# P02_Power_Management.net
KiCad netlist of a schematic drawn in Altium Designer
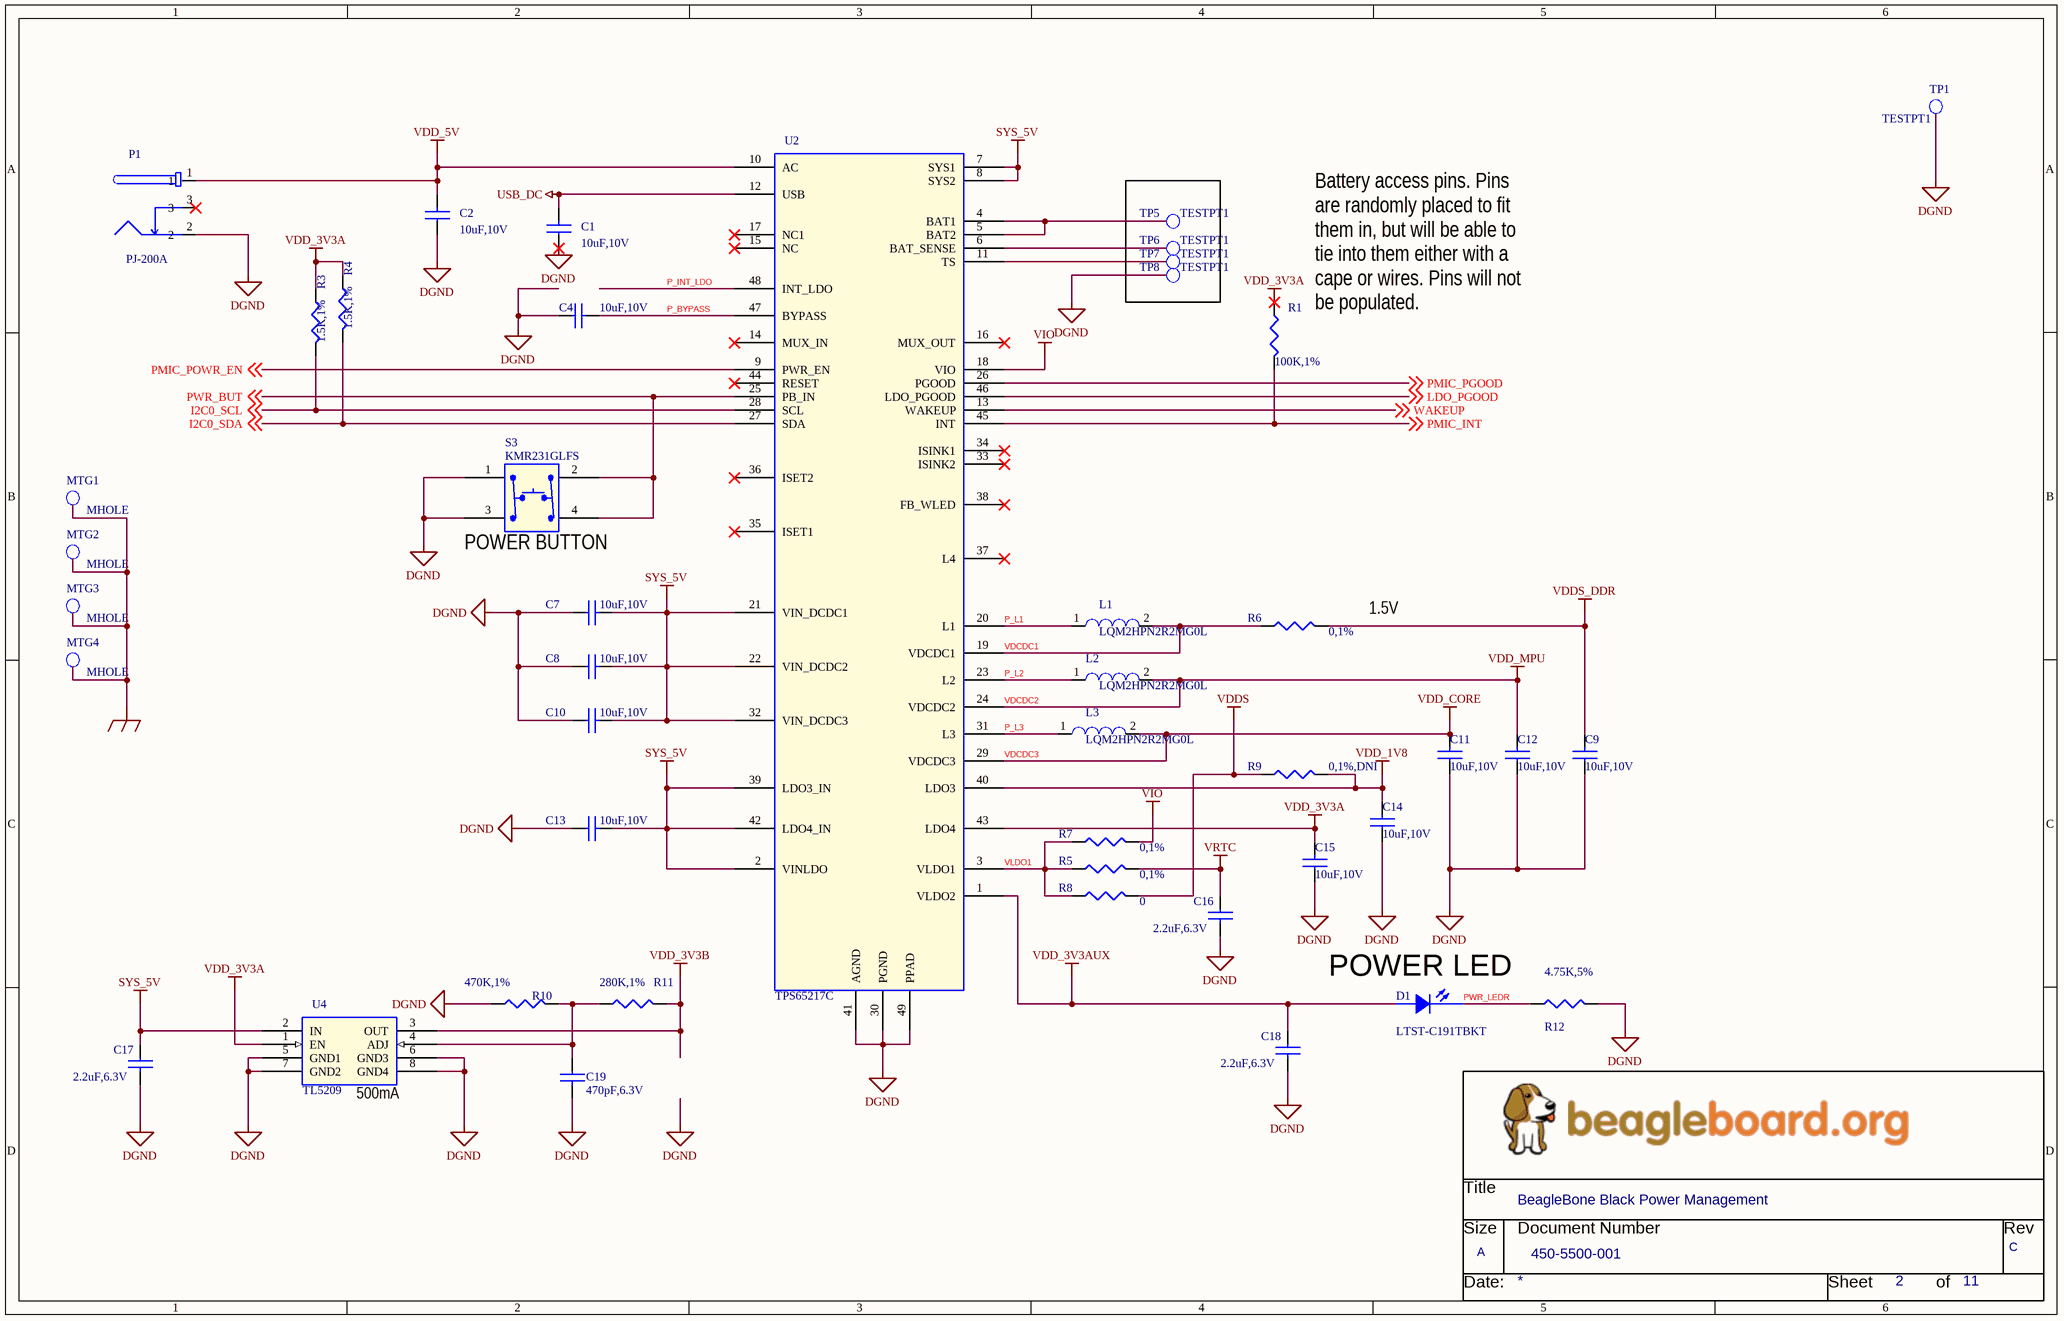
[diagram p0: P02_Power Management.SchDoc]

(export (version "E")
  (design (tool "Eeschema 10.0.6"))
  (components
    (comp (ref "C1")
      (value "10uF,10V")
      (footprint "r402-25rd")
      (fields (field (name "PART NUMBER") "CAP_10uF_Y5V_10V_10%_0805"))
      (libsource (lib "*") (part "CAP_10uF_Y5V_10V_10%_0805"))
    )
    (comp (ref "C2")
      (value "10uF,10V")
      (footprint "r402-25rd")
      (fields (field (name "PART NUMBER") "CAP_10uF_Y5V_10V_10%_0805"))
      (libsource (lib "*") (part "CAP_10uF_Y5V_10V_10%_0805"))
    )
    (comp (ref "C4")
      (value "10uF,10V")
      (footprint "r402-25rd")
      (fields (field (name "PART NUMBER") "CAP_10uF_Y5V_10V_10%_0805"))
      (libsource (lib "*") (part "CAP_10uF_Y5V_10V_10%_0805"))
    )
    (comp (ref "C7")
      (value "10uF,10V")
      (footprint "r402-25rd")
      (fields (field (name "PART NUMBER") "CAP_10uF_Y5V_10V_10%_0805"))
      (libsource (lib "*") (part "CAP_10uF_Y5V_10V_10%_0805"))
    )
    (comp (ref "C8")
      (value "10uF,10V")
      (footprint "r402-25rd")
      (fields (field (name "PART NUMBER") "CAP_10uF_Y5V_10V_10%_0805"))
      (libsource (lib "*") (part "CAP_10uF_Y5V_10V_10%_0805"))
    )
    (comp (ref "C9")
      (value "10uF,10V")
      (footprint "r402-25rd")
      (fields (field (name "PART NUMBER") "CAP_10uF_Y5V_10V_10%_0805"))
      (libsource (lib "*") (part "CAP_10uF_Y5V_10V_10%_0805"))
    )
    (comp (ref "C10")
      (value "10uF,10V")
      (footprint "r402-25rd")
      (fields (field (name "PART NUMBER") "CAP_10uF_Y5V_10V_10%_0805"))
      (libsource (lib "*") (part "CAP_10uF_Y5V_10V_10%_0805"))
    )
    (comp (ref "C11")
      (value "10uF,10V")
      (footprint "r402-25rd")
      (fields (field (name "PART NUMBER") "CAP_10uF_Y5V_10V_10%_0805"))
      (libsource (lib "*") (part "CAP_10uF_Y5V_10V_10%_0805"))
    )
    (comp (ref "C12")
      (value "10uF,10V")
      (footprint "r402-25rd")
      (fields (field (name "PART NUMBER") "CAP_10uF_Y5V_10V_10%_0805"))
      (libsource (lib "*") (part "CAP_10uF_Y5V_10V_10%_0805"))
    )
    (comp (ref "C13")
      (value "10uF,10V")
      (footprint "r402-25rd")
      (fields (field (name "PART NUMBER") "CAP_10uF_Y5V_10V_10%_0805"))
      (libsource (lib "*") (part "CAP_10uF_Y5V_10V_10%_0805"))
    )
    (comp (ref "C14")
      (value "10uF,10V")
      (footprint "r402-25rd")
      (fields (field (name "PART NUMBER") "CAP_10uF_Y5V_10V_10%_0805"))
      (libsource (lib "*") (part "CAP_10uF_Y5V_10V_10%_0805"))
    )
    (comp (ref "C15")
      (value "10uF,10V")
      (footprint "r402-25rd")
      (fields (field (name "PART NUMBER") "CAP_10uF_Y5V_10V_10%_0805"))
      (libsource (lib "*") (part "CAP_10uF_Y5V_10V_10%_0805"))
    )
    (comp (ref "C16")
      (value "2.2uF,6.3V")
      (footprint "402")
      (fields (field (name "PART NUMBER") "CAP_2.2uF_X5R_6.3V_10%_0402"))
      (libsource (lib "*") (part "CAP_2.2uF_X5R_6.3V_10%_0402"))
    )
    (comp (ref "C17")
      (value "2.2uF,6.3V")
      (footprint "402")
      (fields (field (name "PART NUMBER") "CAP_2.2uF_X5R_6.3V_10%_0402"))
      (libsource (lib "*") (part "CAP_2.2uF_X5R_6.3V_10%_0402"))
    )
    (comp (ref "C18")
      (value "2.2uF,6.3V")
      (footprint "402")
      (fields (field (name "PART NUMBER") "CAP_2.2uF_X5R_6.3V_10%_0402"))
      (libsource (lib "*") (part "CAP_2.2uF_X5R_6.3V_10%_0402"))
    )
    (comp (ref "C19")
      (value "470pF,6.3V")
      (footprint "402")
      (fields (field (name "PART NUMBER") "CAP_470PF_X7R_25V_10%_0402"))
      (libsource (lib "*") (part "CAP_470PF_X7R_25V_10%_0402"))
    )
    (comp (ref "D1")
      (value "LTST-C191TBKT")
      (footprint "led1206-59x59")
      (libsource (lib "*") (part "LED_LTST-C150GKT_0"))
    )
    (comp (ref "L1")
      (value "LQM2HPN2R2MG0L")
      (footprint "VLCF5020T")
      (description "Inductor 2.2uH smt 2.6A, 58 milliohm")
      (fields (field (name "TIINTPARTNUMBER") "1L0025") (field (name "MFR") "TDK"))
      (libsource (lib "*") (part "IND_2.2uH_2.6A_10%_SMD"))
    )
    (comp (ref "L2")
      (value "LQM2HPN2R2MG0L")
      (footprint "VLCF5020T")
      (description "Inductor 2.2uH smt 2.6A, 58 milliohm")
      (fields (field (name "TIINTPARTNUMBER") "1L0025") (field (name "MFR") "TDK"))
      (libsource (lib "*") (part "IND_2.2uH_2.6A_10%_SMD"))
    )
    (comp (ref "L3")
      (value "LQM2HPN2R2MG0L")
      (footprint "VLCF5020T")
      (description "Inductor 2.2uH smt 2.6A, 58 milliohm")
      (fields (field (name "TIINTPARTNUMBER") "1L0025") (field (name "MFR") "TDK"))
      (libsource (lib "*") (part "IND_2.2uH_2.6A_10%_SMD"))
    )
    (comp (ref "MTG1") (value "MHOLE") (footprint "mh230-156") (libsource (lib "*") (part "MHOLE")))
    (comp (ref "MTG2") (value "MHOLE") (footprint "mh230-156") (libsource (lib "*") (part "MHOLE")))
    (comp (ref "MTG3") (value "MHOLE") (footprint "mh230-156") (libsource (lib "*") (part "MHOLE")))
    (comp (ref "MTG4") (value "MHOLE") (footprint "mh230-156") (libsource (lib "*") (part "MHOLE")))
    (comp (ref "P1")
      (value "PJ-200A")
      (footprint "CONN3-PWR-PJ102A")
      (libsource (lib "*") (part "Power_Jack"))
    )
    (comp (ref "R1")
      (value "100K,1%")
      (footprint "402")
      (description "Resistor 100Kohm 1/16W 1% 0402")
      (fields (field (name "PART NUMBER") "RES_100K_1/16W_1%_0402"))
      (libsource (lib "*") (part "RES_100K_1/16W_1%_0402"))
    )
    (comp (ref "R3")
      (value "1.5K,1%")
      (footprint "402")
      (description "RES 1.5K OHM 1/16W 5% 0402 SMD")
      (fields (field (name "PART NUMBER") "RES_1.5K_1/16W_5%_0402"))
      (libsource (lib "*") (part "RES_1.5K_1/16W_5%_0402_Dup1"))
    )
    (comp (ref "R4")
      (value "1.5K,1%")
      (footprint "402")
      (description "RES 1.5K OHM 1/16W 5% 0402 SMD")
      (fields (field (name "PART NUMBER") "RES_1.5K_1/16W_5%_0402"))
      (libsource (lib "*") (part "RES_1.5K_1/16W_5%_0402_Dup1"))
    )
    (comp (ref "R5")
      (value "0,1%")
      (footprint "402")
      (description "RES 4.75K OHM 1/16W 1% 0402 SMD")
      (fields (field (name "PART NUMBER") "RES_4.75K_1/16W_1%_0402"))
      (libsource (lib "*") (part "RES_4.75K_1/16W_1%_0402"))
    )
    (comp (ref "R6")
      (value "0,1%")
      (footprint "402")
      (description "RES 4.75K OHM 1/16W 1% 0402 SMD")
      (fields (field (name "PART NUMBER") "RES_4.75K_1/16W_1%_0402"))
      (libsource (lib "*") (part "RES_4.75K_1/16W_1%_0402"))
    )
    (comp (ref "R7")
      (value "0,1%")
      (footprint "402")
      (description "RES 4.75K OHM 1/16W 1% 0402 SMD")
      (fields (field (name "PART NUMBER") "RES_4.75K_1/16W_1%_0402"))
      (libsource (lib "*") (part "RES_4.75K_1/16W_1%_0402"))
    )
    (comp (ref "R8")
      (value "0")
      (footprint "402")
      (description "RES 4.75K OHM 1/16W 1% 0402 SMD")
      (fields (field (name "PART NUMBER") "RES_4.75K_1/16W_1%_0402"))
      (libsource (lib "*") (part "RES_4.75K_1/16W_1%_0402"))
    )
    (comp (ref "R9")
      (value "0,1%,DNI")
      (footprint "402")
      (description "RES 4.75K OHM 1/16W 1% 0402 SMD")
      (fields (field (name "PART NUMBER") "RES_4.75K_1/16W_1%_0402"))
      (libsource (lib "*") (part "RES_4.75K_1/16W_1%_0402"))
    )
    (comp (ref "R10")
      (value "470K,1%")
      (footprint "402")
      (description "RES 470 OHM 1/10W 5% 0402 SMD")
      (fields (field (name "PART NUMBER") "RES_470_1/10W_5%_0402"))
      (libsource (lib "*") (part "RES_470_1/10W_5%_0402"))
    )
    (comp (ref "R11")
      (value "280K,1%")
      (footprint "402")
      (description "RES 470 OHM 1/10W 5% 0402 SMD")
      (fields (field (name "PART NUMBER") "RES_470_1/10W_5%_0402"))
      (libsource (lib "*") (part "RES_470_1/10W_5%_0402"))
    )
    (comp (ref "R12")
      (value "4.75K,5%")
      (footprint "402")
      (description "RES 470 OHM 1/10W 5% 0402 SMD")
      (fields (field (name "PART NUMBER") "RES_470_1/10W_5%_0402"))
      (libsource (lib "*") (part "RES_470_1/10W_5%_0402"))
    )
    (comp (ref "S3")
      (value "KMR231GLFS")
      (footprint "SM-SW-SPST-4-4")
      (libsource (lib "*") (part "SW_KT11P2JM_2"))
    )
    (comp (ref "TP1") (value "TESTPT1") (footprint "tp1-8040") (libsource (lib "*") (part "TESTPT1")))
    (comp (ref "TP5") (value "TESTPT1") (footprint "tp1-8040") (libsource (lib "*") (part "TESTPT1")))
    (comp (ref "TP6") (value "TESTPT1") (footprint "tp1-8040") (libsource (lib "*") (part "TESTPT1")))
    (comp (ref "TP7") (value "TESTPT1") (footprint "tp1-8040") (libsource (lib "*") (part "TESTPT1")))
    (comp (ref "TP8") (value "TESTPT1") (footprint "tp1-8040") (libsource (lib "*") (part "TESTPT1")))
    (comp (ref "U2") (value "TPS65217C") (footprint "TBD") (libsource (lib "*") (part "PWR_TPS65217_2")))
    (comp (ref "U4")
      (value "TL5209")
      (footprint "SO8-25X75")
      (libsource (lib "*") (part "PWR_TLV70233DBV_0"))
    )
  )
  (nets
    (net (code "1") (name "/PWR_LEDR") (class "Default")
      (node (ref "D1") (pin "1") (pinfunction "C_1") (pintype "passive"))
      (node (ref "R12") (pin "2") (pinfunction "2_2") (pintype "passive"))
    )
    (net (code "2") (name "/P_BYPASS") (class "Default")
      (node (ref "C4") (pin "2") (pinfunction "2_2") (pintype "passive"))
      (node (ref "U2") (pin "47") (pinfunction "BYPASS_47") (pintype "passive"))
    )
    (net (code "3") (name "/P_INT_LDO") (class "Default")
      (node (ref "U2") (pin "48") (pinfunction "INT_LDO_48") (pintype "passive"))
    )
    (net (code "4") (name "/P_L1") (class "Default")
      (node (ref "L1") (pin "1") (pinfunction "1_1") (pintype "passive"))
      (node (ref "U2") (pin "20") (pinfunction "L1_20") (pintype "passive"))
    )
    (net (code "5") (name "/P_L2") (class "Default")
      (node (ref "L2") (pin "1") (pinfunction "1_1") (pintype "passive"))
      (node (ref "U2") (pin "23") (pinfunction "L2_23") (pintype "passive"))
    )
    (net (code "6") (name "/P_L3") (class "Default")
      (node (ref "L3") (pin "1") (pinfunction "1_1") (pintype "passive"))
      (node (ref "U2") (pin "31") (pinfunction "L3_31") (pintype "passive"))
    )
    (net (code "7") (name "/VDCDC1") (class "Default")
      (node (ref "L1") (pin "2") (pinfunction "2_2") (pintype "passive"))
      (node (ref "R6") (pin "1") (pinfunction "1_1") (pintype "passive"))
      (node (ref "U2") (pin "19") (pinfunction "VDCDC1_19") (pintype "passive"))
    )
    (net (code "8") (name "/VLDO1") (class "Default")
      (node (ref "R5") (pin "1") (pinfunction "1_1") (pintype "passive"))
      (node (ref "R7") (pin "1") (pinfunction "1_1") (pintype "passive"))
      (node (ref "R8") (pin "1") (pinfunction "1_1") (pintype "passive"))
      (node (ref "U2") (pin "3") (pinfunction "VLDO1_3") (pintype "passive"))
    )
    (net (code "9") (name "DGND") (class "Default")
      (node (ref "C1") (pin "1") (pinfunction "1_1") (pintype "passive"))
      (node (ref "C10") (pin "1") (pinfunction "1_1") (pintype "passive"))
      (node (ref "C11") (pin "1") (pinfunction "1_1") (pintype "passive"))
      (node (ref "C12") (pin "1") (pinfunction "1_1") (pintype "passive"))
      (node (ref "C13") (pin "1") (pinfunction "1_1") (pintype "passive"))
      (node (ref "C14") (pin "1") (pinfunction "1_1") (pintype "passive"))
      (node (ref "C15") (pin "1") (pinfunction "1_1") (pintype "passive"))
      (node (ref "C16") (pin "2") (pinfunction "2_2") (pintype "passive"))
      (node (ref "C17") (pin "2") (pinfunction "2_2") (pintype "passive"))
      (node (ref "C18") (pin "2") (pinfunction "2_2") (pintype "passive"))
      (node (ref "C19") (pin "2") (pinfunction "2_2") (pintype "passive"))
      (node (ref "C2") (pin "1") (pinfunction "1_1") (pintype "passive"))
      (node (ref "C4") (pin "1") (pinfunction "1_1") (pintype "passive"))
      (node (ref "C7") (pin "1") (pinfunction "1_1") (pintype "passive"))
      (node (ref "C8") (pin "1") (pinfunction "1_1") (pintype "passive"))
      (node (ref "C9") (pin "1") (pinfunction "1_1") (pintype "passive"))
      (node (ref "P1") (pin "2") (pinfunction "2_2") (pintype "passive"))
      (node (ref "R10") (pin "2") (pinfunction "2_2") (pintype "passive"))
      (node (ref "R12") (pin "1") (pinfunction "1_1") (pintype "passive"))
      (node (ref "S3") (pin "1") (pinfunction "A1_1") (pintype "passive"))
      (node (ref "S3") (pin "3") (pinfunction "A2_3") (pintype "passive"))
      (node (ref "TP1") (pin "1") (pinfunction "TP_1") (pintype "passive"))
      (node (ref "TP8") (pin "1") (pinfunction "TP_1") (pintype "passive"))
      (node (ref "U2") (pin "30") (pinfunction "PGND_30") (pintype "passive"))
      (node (ref "U2") (pin "41") (pinfunction "AGND_41") (pintype "passive"))
      (node (ref "U2") (pin "49") (pinfunction "PPAD_49") (pintype "passive"))
      (node (ref "U4") (pin "5") (pinfunction "GND1_5") (pintype "power_in"))
      (node (ref "U4") (pin "6") (pinfunction "GND3_6") (pintype "power_in"))
      (node (ref "U4") (pin "7") (pinfunction "GND2_7") (pintype "power_in"))
      (node (ref "U4") (pin "8") (pinfunction "GND4_8") (pintype "power_in"))
    )
    (net (code "10") (name "GND_EARTH") (class "Default")
      (node (ref "MTG1") (pin "1") (pinfunction "TP_1") (pintype "passive"))
      (node (ref "MTG2") (pin "1") (pinfunction "TP_1") (pintype "passive"))
      (node (ref "MTG3") (pin "1") (pinfunction "TP_1") (pintype "passive"))
      (node (ref "MTG4") (pin "1") (pinfunction "TP_1") (pintype "passive"))
    )
    (net (code "11") (name "I2C0_SCL") (class "Default")
      (node (ref "R3") (pin "2") (pinfunction "2_2") (pintype "passive"))
      (node (ref "U2") (pin "28") (pinfunction "SCL_28") (pintype "passive"))
    )
    (net (code "12") (name "I2C0_SDA") (class "Default")
      (node (ref "R4") (pin "2") (pinfunction "2_2") (pintype "passive"))
      (node (ref "U2") (pin "27") (pinfunction "SDA_27") (pintype "passive"))
    )
    (net (code "13") (name "LDO_PGOOD") (class "Default")
      (node (ref "U2") (pin "46") (pinfunction "LDO_PGOOD_46") (pintype "passive"))
    )
    (net (code "14") (name "Net-(TP5-TP)") (class "Default")
      (node (ref "TP5") (pin "1") (pinfunction "TP_1") (pintype "passive"))
      (node (ref "U2") (pin "4") (pinfunction "BAT1_4") (pintype "passive"))
      (node (ref "U2") (pin "5") (pinfunction "BAT2_5") (pintype "passive"))
    )
    (net (code "15") (name "Net-(TP6-TP)") (class "Default")
      (node (ref "TP6") (pin "1") (pinfunction "TP_1") (pintype "passive"))
      (node (ref "U2") (pin "6") (pinfunction "BAT_SENSE_6") (pintype "passive"))
    )
    (net (code "16") (name "Net-(TP7-TP)") (class "Default")
      (node (ref "TP7") (pin "1") (pinfunction "TP_1") (pintype "passive"))
      (node (ref "U2") (pin "11") (pinfunction "TS_11") (pintype "passive"))
    )
    (net (code "17") (name "Net-(U4-ADJ)") (class "Default")
      (node (ref "C19") (pin "1") (pinfunction "1_1") (pintype "passive"))
      (node (ref "R10") (pin "1") (pinfunction "1_1") (pintype "passive"))
      (node (ref "R11") (pin "2") (pinfunction "2_2") (pintype "passive"))
      (node (ref "U4") (pin "4") (pinfunction "ADJ_4") (pintype "input"))
    )
    (net (code "18") (name "PMIC_INT") (class "Default")
      (node (ref "R1") (pin "2") (pinfunction "2_2") (pintype "passive"))
      (node (ref "U2") (pin "45") (pinfunction "INT_45") (pintype "passive"))
    )
    (net (code "19") (name "PMIC_PGOOD") (class "Default")
      (node (ref "U2") (pin "26") (pinfunction "PGOOD_26") (pintype "passive"))
    )
    (net (code "20") (name "PMIC_POWR_EN") (class "Default")
      (node (ref "U2") (pin "9") (pinfunction "PWR_EN_9") (pintype "passive"))
    )
    (net (code "21") (name "PWR_BUT") (class "Default")
      (node (ref "S3") (pin "2") (pinfunction "B1_2") (pintype "passive"))
      (node (ref "S3") (pin "4") (pinfunction "B2_4") (pintype "passive"))
      (node (ref "U2") (pin "25") (pinfunction "PB_IN_25") (pintype "passive"))
    )
    (net (code "22") (name "SYS_5V") (class "Default")
      (node (ref "C10") (pin "2") (pinfunction "2_2") (pintype "passive"))
      (node (ref "C13") (pin "2") (pinfunction "2_2") (pintype "passive"))
      (node (ref "C17") (pin "1") (pinfunction "1_1") (pintype "passive"))
      (node (ref "C7") (pin "2") (pinfunction "2_2") (pintype "passive"))
      (node (ref "C8") (pin "2") (pinfunction "2_2") (pintype "passive"))
      (node (ref "U2") (pin "2") (pinfunction "VINLDO_2") (pintype "passive"))
      (node (ref "U2") (pin "21") (pinfunction "VIN_DCDC1_21") (pintype "passive"))
      (node (ref "U2") (pin "22") (pinfunction "VIN_DCDC2_22") (pintype "passive"))
      (node (ref "U2") (pin "32") (pinfunction "VIN_DCDC3_32") (pintype "passive"))
      (node (ref "U2") (pin "39") (pinfunction "LDO3_IN_39") (pintype "passive"))
      (node (ref "U2") (pin "42") (pinfunction "LDO4_IN_42") (pintype "passive"))
      (node (ref "U2") (pin "7") (pinfunction "SYS1_7") (pintype "passive"))
      (node (ref "U2") (pin "8") (pinfunction "SYS2_8") (pintype "passive"))
      (node (ref "U4") (pin "2") (pinfunction "IN_2") (pintype "power_in"))
    )
    (net (code "23") (name "USB_DC") (class "Default")
      (node (ref "C1") (pin "2") (pinfunction "2_2") (pintype "passive"))
      (node (ref "U2") (pin "12") (pinfunction "USB_12") (pintype "passive"))
    )
    (net (code "24") (name "VDDS") (class "Default")
      (node (ref "R8") (pin "2") (pinfunction "2_2") (pintype "passive"))
      (node (ref "R9") (pin "1") (pinfunction "1_1") (pintype "passive"))
    )
    (net (code "25") (name "VDDS_DDR") (class "Default")
      (node (ref "C9") (pin "2") (pinfunction "2_2") (pintype "passive"))
      (node (ref "R6") (pin "2") (pinfunction "2_2") (pintype "passive"))
    )
    (net (code "26") (name "VDD_1V8") (class "Default")
      (node (ref "C14") (pin "2") (pinfunction "2_2") (pintype "passive"))
      (node (ref "R9") (pin "2") (pinfunction "2_2") (pintype "passive"))
      (node (ref "U2") (pin "40") (pinfunction "LDO3_40") (pintype "passive"))
    )
    (net (code "27") (name "VDD_3V3A") (class "Default")
      (node (ref "C15") (pin "2") (pinfunction "2_2") (pintype "passive"))
      (node (ref "R1") (pin "1") (pinfunction "1_1") (pintype "passive"))
      (node (ref "R3") (pin "1") (pinfunction "1_1") (pintype "passive"))
      (node (ref "R4") (pin "1") (pinfunction "1_1") (pintype "passive"))
      (node (ref "U2") (pin "43") (pinfunction "LDO4_43") (pintype "passive"))
      (node (ref "U4") (pin "1") (pinfunction "EN_1") (pintype "input"))
    )
    (net (code "28") (name "VDD_3V3AUX") (class "Default")
      (node (ref "C18") (pin "1") (pinfunction "1_1") (pintype "passive"))
      (node (ref "D1") (pin "2") (pinfunction "A_2") (pintype "passive"))
      (node (ref "U2") (pin "1") (pinfunction "VLDO2_1") (pintype "passive"))
    )
    (net (code "29") (name "VDD_3V3B") (class "Default")
      (node (ref "R11") (pin "1") (pinfunction "1_1") (pintype "passive"))
      (node (ref "U4") (pin "3") (pinfunction "OUT_3") (pintype "power_in"))
    )
    (net (code "30") (name "VDD_5V") (class "Default")
      (node (ref "C2") (pin "2") (pinfunction "2_2") (pintype "passive"))
      (node (ref "P1") (pin "1") (pinfunction "1_1") (pintype "passive"))
      (node (ref "U2") (pin "10") (pinfunction "AC_10") (pintype "passive"))
    )
    (net (code "31") (name "VDD_CORE") (class "Default")
      (node (ref "C11") (pin "2") (pinfunction "2_2") (pintype "passive"))
      (node (ref "L3") (pin "2") (pinfunction "2_2") (pintype "passive"))
      (node (ref "U2") (pin "29") (pinfunction "VDCDC3_29") (pintype "passive"))
    )
    (net (code "32") (name "VDD_MPU") (class "Default")
      (node (ref "C12") (pin "2") (pinfunction "2_2") (pintype "passive"))
      (node (ref "L2") (pin "2") (pinfunction "2_2") (pintype "passive"))
      (node (ref "U2") (pin "24") (pinfunction "VDCDC2_24") (pintype "passive"))
    )
    (net (code "33") (name "VIO") (class "Default")
      (node (ref "R7") (pin "2") (pinfunction "2_2") (pintype "passive"))
      (node (ref "U2") (pin "18") (pinfunction "VIO_18") (pintype "passive"))
    )
    (net (code "34") (name "VRTC") (class "Default")
      (node (ref "C16") (pin "1") (pinfunction "1_1") (pintype "passive"))
      (node (ref "R5") (pin "2") (pinfunction "2_2") (pintype "passive"))
    )
    (net (code "35") (name "WAKEUP") (class "Default")
      (node (ref "U2") (pin "13") (pinfunction "WAKEUP_13") (pintype "passive"))
    )
    (net (code "36") (name "unconnected-(P1-Pad3)") (class "Default")
      (node (ref "P1") (pin "3") (pinfunction "3_3") (pintype "passive+no_connect"))
    )
    (net (code "37") (name "unconnected-(U2-FB_WLED-Pad38)") (class "Default")
      (node (ref "U2") (pin "38") (pinfunction "FB_WLED_38") (pintype "passive+no_connect"))
    )
    (net (code "38") (name "unconnected-(U2-ISET1-Pad35)") (class "Default")
      (node (ref "U2") (pin "35") (pinfunction "ISET1_35") (pintype "passive+no_connect"))
    )
    (net (code "39") (name "unconnected-(U2-ISET2-Pad36)") (class "Default")
      (node (ref "U2") (pin "36") (pinfunction "ISET2_36") (pintype "passive+no_connect"))
    )
    (net (code "40") (name "unconnected-(U2-ISINK1-Pad34)") (class "Default")
      (node (ref "U2") (pin "34") (pinfunction "ISINK1_34") (pintype "passive+no_connect"))
    )
    (net (code "41") (name "unconnected-(U2-ISINK2-Pad33)") (class "Default")
      (node (ref "U2") (pin "33") (pinfunction "ISINK2_33") (pintype "passive+no_connect"))
    )
    (net (code "42") (name "unconnected-(U2-L4-Pad37)") (class "Default")
      (node (ref "U2") (pin "37") (pinfunction "L4_37") (pintype "passive+no_connect"))
    )
    (net (code "43") (name "unconnected-(U2-MUX_IN-Pad14)") (class "Default")
      (node (ref "U2") (pin "14") (pinfunction "MUX_IN_14") (pintype "passive+no_connect"))
    )
    (net (code "44") (name "unconnected-(U2-MUX_OUT-Pad16)") (class "Default")
      (node (ref "U2") (pin "16") (pinfunction "MUX_OUT_16") (pintype "passive+no_connect"))
    )
    (net (code "45") (name "unconnected-(U2-NC-Pad15)") (class "Default")
      (node (ref "U2") (pin "15") (pinfunction "NC_15") (pintype "passive+no_connect"))
    )
    (net (code "46") (name "unconnected-(U2-NC1-Pad17)") (class "Default")
      (node (ref "U2") (pin "17") (pinfunction "NC1_17") (pintype "passive+no_connect"))
    )
    (net (code "47") (name "unconnected-(U2-RESET-Pad44)") (class "Default")
      (node (ref "U2") (pin "44") (pinfunction "RESET_44") (pintype "passive+no_connect"))
    )
  )
)
